# 04_-_CONTROL.net
KiCad netlist of a schematic drawn in Altium Designer
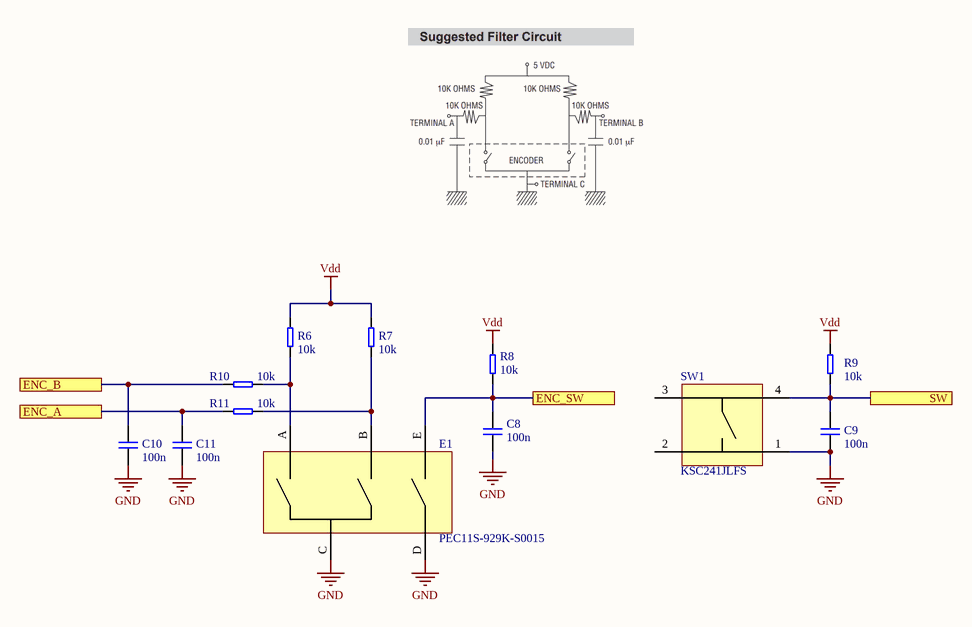
[diagram p0: [04] - CONTROL.SchDoc]

(export (version "E")
  (design (tool "Eeschema 10.0.6"))
  (components
    (comp (ref "C8")
      (value "100n")
      (footprint "C0603")
      (description "CAPACITOR")
      (libsource (lib "1") (part "Cap"))
    )
    (comp (ref "C9")
      (value "100n")
      (footprint "C0603")
      (description "CAPACITOR")
      (libsource (lib "1") (part "Cap"))
    )
    (comp (ref "C10")
      (value "100n")
      (footprint "C0603")
      (description "CAPACITOR")
      (libsource (lib "1") (part "Cap"))
    )
    (comp (ref "C11")
      (value "100n")
      (footprint "C0603")
      (description "CAPACITOR")
      (libsource (lib "1") (part "Cap"))
    )
    (comp (ref "E1")
      (value "PEC11S-929K-S0015")
      (footprint "PEC11S-929K-S0015")
      (description "ROTARY ENCODER MECHANICAL 15PPR")
      (fields (field (name "MANUFACTURER") "Bourns"))
      (libsource (lib "1") (part "PEC11S-929K-S0015"))
    )
    (comp (ref "R6")
      (value "10k")
      (footprint "R0603")
      (description "RESISTOR")
      (libsource (lib "1") (part "Res"))
    )
    (comp (ref "R7")
      (value "10k")
      (footprint "R0603")
      (description "RESISTOR")
      (libsource (lib "1") (part "Res"))
    )
    (comp (ref "R8")
      (value "10k")
      (footprint "R0603")
      (description "RESISTOR")
      (libsource (lib "1") (part "Res"))
    )
    (comp (ref "R9")
      (value "10k")
      (footprint "R0603")
      (description "RESISTOR")
      (libsource (lib "1") (part "Res"))
    )
    (comp (ref "R10")
      (value "10k")
      (footprint "R0603")
      (description "RESISTOR")
      (libsource (lib "1") (part "Res"))
    )
    (comp (ref "R11")
      (value "10k")
      (footprint "R0603")
      (description "RESISTOR")
      (libsource (lib "1") (part "Res"))
    )
    (comp (ref "SW1")
      (value "KSC241JLFS")
      (footprint "KSC241JLFS")
      (description "SWITCH TACTILE SPST-NO 50mA @ 32VDC")
      (fields (field (name "MANUFACTURER") "C&K"))
      (libsource (lib "1") (part "KSC241JLFS"))
    )
  )
  (nets
    (net (code "1") (name "/ENC_A") (class "Default")
      (node (ref "C11") (pin "2") (pinfunction "2_2") (pintype "passive"))
      (node (ref "R11") (pin "2") (pinfunction "2_2") (pintype "passive"))
    )
    (net (code "2") (name "/ENC_B") (class "Default")
      (node (ref "C10") (pin "2") (pinfunction "2_2") (pintype "passive"))
      (node (ref "R10") (pin "2") (pinfunction "2_2") (pintype "passive"))
    )
    (net (code "3") (name "/ENC_SW") (class "Default")
      (node (ref "C8") (pin "2") (pinfunction "2_2") (pintype "passive"))
      (node (ref "E1") (pin "E") (pinfunction "2_E") (pintype "passive"))
      (node (ref "R8") (pin "1") (pinfunction "1_1") (pintype "passive"))
    )
    (net (code "4") (name "/SW") (class "Default")
      (node (ref "C9") (pin "2") (pinfunction "2_2") (pintype "passive"))
      (node (ref "R9") (pin "1") (pinfunction "1_1") (pintype "passive"))
      (node (ref "SW1") (pin "4") (pinfunction "4_4") (pintype "passive"))
    )
    (net (code "5") (name "GND") (class "Default")
      (node (ref "C10") (pin "1") (pinfunction "1_1") (pintype "passive"))
      (node (ref "C11") (pin "1") (pinfunction "1_1") (pintype "passive"))
      (node (ref "C8") (pin "1") (pinfunction "1_1") (pintype "passive"))
      (node (ref "C9") (pin "1") (pinfunction "1_1") (pintype "passive"))
      (node (ref "E1") (pin "C") (pinfunction "C_C") (pintype "passive"))
      (node (ref "E1") (pin "D") (pinfunction "1_D") (pintype "passive"))
      (node (ref "SW1") (pin "1") (pinfunction "1_1") (pintype "passive"))
    )
    (net (code "6") (name "Net-(E1-PadA)") (class "Default")
      (node (ref "E1") (pin "A") (pinfunction "A_A") (pintype "passive"))
      (node (ref "R10") (pin "1") (pinfunction "1_1") (pintype "passive"))
      (node (ref "R6") (pin "1") (pinfunction "1_1") (pintype "passive"))
    )
    (net (code "7") (name "Net-(E1-PadB)") (class "Default")
      (node (ref "E1") (pin "B") (pinfunction "B_B") (pintype "passive"))
      (node (ref "R11") (pin "1") (pinfunction "1_1") (pintype "passive"))
      (node (ref "R7") (pin "1") (pinfunction "1_1") (pintype "passive"))
    )
    (net (code "8") (name "Vdd") (class "Default")
      (node (ref "R6") (pin "2") (pinfunction "2_2") (pintype "passive"))
      (node (ref "R7") (pin "2") (pinfunction "2_2") (pintype "passive"))
      (node (ref "R8") (pin "2") (pinfunction "2_2") (pintype "passive"))
      (node (ref "R9") (pin "2") (pinfunction "2_2") (pintype "passive"))
    )
    (net (code "9") (name "unconnected-(SW1-Pad2)") (class "Default")
      (node (ref "SW1") (pin "2") (pinfunction "2_2") (pintype "passive"))
    )
    (net (code "10") (name "unconnected-(SW1-Pad3)") (class "Default")
      (node (ref "SW1") (pin "3") (pinfunction "3_3") (pintype "passive"))
    )
  )
)
